# SCH.net
KiCad netlist of a schematic drawn in Altium Designer
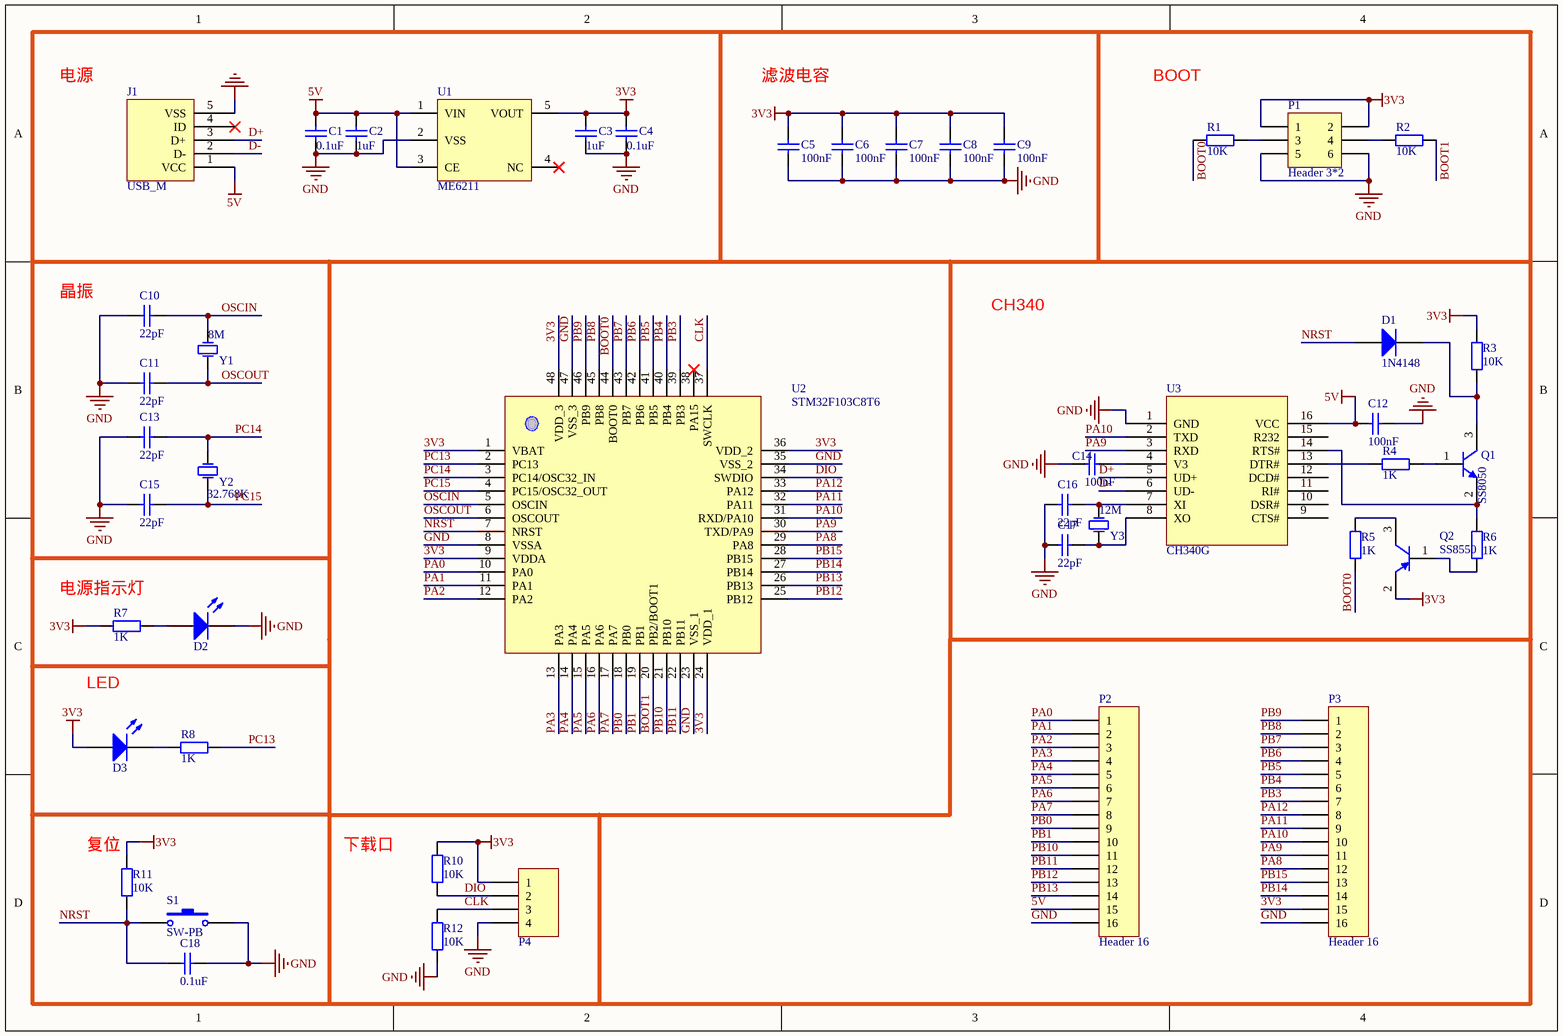
[diagram p0: SCH.SchDoc]

(export (version "E")
  (design (tool "Eeschema 10.0.6"))
  (components
    (comp (ref "C1")
      (value "0.1uF")
      (footprint "0603_C")
      (description "贴片电容")
      (fields (field (name "Comment") "Cap"))
      (libsource (lib "Miscellaneous Devices LC (1)") (part "0603 1uF (105) 10% 50V"))
    )
    (comp (ref "C2")
      (value "1uF")
      (footprint "0603_C")
      (description "贴片电容")
      (fields (field (name "Comment") "Cap"))
      (libsource (lib "Miscellaneous Devices LC (1)") (part "0603 1uF (105) 10% 50V"))
    )
    (comp (ref "C3")
      (value "1uF")
      (footprint "0603_C")
      (description "贴片电容")
      (fields (field (name "Comment") "Cap"))
      (libsource (lib "Miscellaneous Devices LC (1)") (part "0603 1uF (105) 10% 50V"))
    )
    (comp (ref "C4")
      (value "0.1uF")
      (footprint "0603_C")
      (description "贴片电容")
      (fields (field (name "Comment") "Cap"))
      (libsource (lib "Miscellaneous Devices LC (1)") (part "0603 1uF (105) 10% 50V"))
    )
    (comp (ref "C5")
      (value "100nF")
      (footprint "0603_C")
      (description "无极性电容")
      (fields (field (name "Comment") "Cap") (field (name "PUBLISHER") "Altium Limited"))
      (libsource (lib "fszhang") (part "Cap"))
    )
    (comp (ref "C6")
      (value "100nF")
      (footprint "0603_C")
      (description "无极性电容")
      (fields (field (name "Comment") "Cap") (field (name "PUBLISHER") "Altium Limited"))
      (libsource (lib "fszhang") (part "Cap"))
    )
    (comp (ref "C7")
      (value "100nF")
      (footprint "0603_C")
      (description "无极性电容")
      (fields (field (name "Comment") "Cap") (field (name "PUBLISHER") "Altium Limited"))
      (libsource (lib "fszhang") (part "Cap"))
    )
    (comp (ref "C8")
      (value "100nF")
      (footprint "0603_C")
      (description "无极性电容")
      (fields (field (name "Comment") "Cap") (field (name "PUBLISHER") "Altium Limited"))
      (libsource (lib "fszhang") (part "Cap"))
    )
    (comp (ref "C9")
      (value "100nF")
      (footprint "0603_C")
      (description "无极性电容")
      (fields (field (name "Comment") "Cap") (field (name "PUBLISHER") "Altium Limited"))
      (libsource (lib "fszhang") (part "Cap"))
    )
    (comp (ref "C10")
      (value "22pF")
      (footprint "0603_C")
      (description "无极性电容")
      (fields (field (name "Comment") "Cap") (field (name "PUBLISHER") "Altium Limited"))
      (libsource (lib "fszhang") (part "Cap"))
    )
    (comp (ref "C11")
      (value "22pF")
      (footprint "0603_C")
      (description "无极性电容")
      (fields (field (name "Comment") "Cap") (field (name "PUBLISHER") "Altium Limited"))
      (libsource (lib "fszhang") (part "Cap"))
    )
    (comp (ref "C12")
      (value "100nF")
      (footprint "0603_C")
      (description "无极性电容")
      (fields (field (name "Comment") "Cap") (field (name "PUBLISHER") "Altium Limited"))
      (libsource (lib "fszhang") (part "Cap"))
    )
    (comp (ref "C13")
      (value "22pF")
      (footprint "0603_C")
      (description "无极性电容")
      (fields (field (name "Comment") "Cap") (field (name "PUBLISHER") "Altium Limited"))
      (libsource (lib "fszhang") (part "Cap"))
    )
    (comp (ref "C14")
      (value "100nF")
      (footprint "0603_C")
      (description "无极性电容")
      (fields (field (name "Comment") "Cap") (field (name "PUBLISHER") "Altium Limited"))
      (libsource (lib "fszhang") (part "Cap"))
    )
    (comp (ref "C15")
      (value "22pF")
      (footprint "0603_C")
      (description "无极性电容")
      (fields (field (name "Comment") "Cap") (field (name "PUBLISHER") "Altium Limited"))
      (libsource (lib "fszhang") (part "Cap"))
    )
    (comp (ref "C16")
      (value "22pF")
      (footprint "0603_C")
      (description "无极性电容")
      (fields (field (name "Comment") "Cap") (field (name "PUBLISHER") "Altium Limited"))
      (libsource (lib "fszhang") (part "Cap"))
    )
    (comp (ref "C17")
      (value "22pF")
      (footprint "0603_C")
      (description "无极性电容")
      (fields (field (name "Comment") "Cap") (field (name "PUBLISHER") "Altium Limited"))
      (libsource (lib "fszhang") (part "Cap"))
    )
    (comp (ref "C18")
      (value "0.1uF")
      (footprint "0603_C")
      (description "贴片电容")
      (fields (field (name "Comment") "Cap"))
      (libsource (lib "Miscellaneous Devices LC (1)") (part "0603 1uF (105) 10% 50V"))
    )
    (comp (ref "D1")
      (value "Diode")
      (footprint "SOD-323")
      (description "二极管")
      (fields (field (name "TYPE") "1N4148") (field (name "PUBLISHER") "Altium Limited"))
      (libsource (lib "fszhang") (part "Diode"))
    )
    (comp (ref "D2")
      (value "LED0")
      (footprint "LED_0805_Blue")
      (description "发光二极管")
      (fields (field (name "PUBLISHER") "Altium Limited"))
      (libsource (lib "fszhang") (part "LED0"))
    )
    (comp (ref "D3")
      (value "LED0")
      (footprint "LED_0805_Blue")
      (description "发光二极管")
      (fields (field (name "PUBLISHER") "Altium Limited"))
      (libsource (lib "fszhang") (part "LED0"))
    )
    (comp (ref "J1")
      (value "USB_M")
      (footprint "USB")
      (description "MicroUSB接口")
      (libsource (lib "fszhang") (part "USB_M"))
    )
    (comp (ref "P1")
      (value "Header 3*2")
      (footprint "HDR3X2")
      (description "接插件")
      (libsource (lib "fszhang") (part "Header 3*2"))
    )
    (comp (ref "P2")
      (value "Header 16")
      (footprint "HDR16X1_A")
      (description "Header16贴片")
      (fields (field (name "PUBLISHER") "Altium Limited"))
      (libsource (lib "fszhang") (part "Header 16"))
    )
    (comp (ref "P3")
      (value "Header 16")
      (footprint "HDR16X1_A")
      (description "Header16贴片")
      (fields (field (name "PUBLISHER") "Altium Limited"))
      (libsource (lib "fszhang") (part "Header 16"))
    )
    (comp (ref "P4")
      (value "Header 4")
      (footprint "HDR4X1_A")
      (description "接插件")
      (fields (field (name "PUBLISHER") "Altium Limited"))
      (libsource (lib "fszhang") (part "Header 4"))
    )
    (comp (ref "Q1")
      (value "SS8050")
      (footprint "SOT-23")
      (description "NPN贴片三极管")
      (fields (field (name "PUBLISHER") "Altium Limited"))
      (libsource (lib "fszhang") (part "SS8050"))
    )
    (comp (ref "Q2")
      (value "SS8550")
      (footprint "SOT-23")
      (description "PNP贴片三极管")
      (fields (field (name "PUBLISHER") "Altium Limited"))
      (libsource (lib "fszhang") (part "SS8550"))
    )
    (comp (ref "R1")
      (value "10K")
      (footprint "0603_R")
      (description "贴片电阻")
      (fields (field (name "Comment") "Res1") (field (name "PUBLISHER") "Altium Limited"))
      (libsource (lib "") (part "Res1_3"))
    )
    (comp (ref "R2")
      (value "10K")
      (footprint "0603_R")
      (description "贴片电阻")
      (fields (field (name "Comment") "Res1") (field (name "PUBLISHER") "Altium Limited"))
      (libsource (lib "") (part "Res1_3"))
    )
    (comp (ref "R3")
      (value "10K")
      (footprint "0603_R")
      (description "贴片电阻")
      (fields (field (name "Comment") "Res1") (field (name "PUBLISHER") "Altium Limited"))
      (libsource (lib "fszhang") (part "Res1"))
    )
    (comp (ref "R4")
      (value "1K")
      (footprint "0603_R")
      (description "贴片电阻")
      (fields (field (name "Comment") "Res1") (field (name "PUBLISHER") "Altium Limited"))
      (libsource (lib "") (part "Res1_3"))
    )
    (comp (ref "R5")
      (value "1K")
      (footprint "0603_R")
      (description "贴片电阻")
      (fields (field (name "Comment") "Res1") (field (name "PUBLISHER") "Altium Limited"))
      (libsource (lib "fszhang") (part "Res1"))
    )
    (comp (ref "R6")
      (value "1K")
      (footprint "0603_R")
      (description "贴片电阻")
      (fields (field (name "Comment") "Res1") (field (name "PUBLISHER") "Altium Limited"))
      (libsource (lib "fszhang") (part "Res1"))
    )
    (comp (ref "R7")
      (value "1K")
      (footprint "0603_R")
      (description "贴片电阻")
      (fields (field (name "Comment") "Res1") (field (name "PUBLISHER") "Altium Limited"))
      (libsource (lib "") (part "Res1_2"))
    )
    (comp (ref "R8")
      (value "1K")
      (footprint "0603_R")
      (description "贴片电阻")
      (fields (field (name "Comment") "Res1") (field (name "PUBLISHER") "Altium Limited"))
      (libsource (lib "") (part "Res1_2"))
    )
    (comp (ref "R10")
      (value "10K")
      (footprint "0603_R")
      (description "贴片电阻")
      (fields (field (name "Comment") "Res1") (field (name "PUBLISHER") "Altium Limited"))
      (libsource (lib "") (part "Res1_1"))
    )
    (comp (ref "R11")
      (value "10K")
      (footprint "0603_R")
      (description "贴片电阻")
      (fields (field (name "Comment") "Res1") (field (name "PUBLISHER") "Altium Limited"))
      (libsource (lib "fszhang") (part "Res1"))
    )
    (comp (ref "R12")
      (value "10K")
      (footprint "0603_R")
      (description "贴片电阻")
      (fields (field (name "Comment") "Res1") (field (name "PUBLISHER") "Altium Limited"))
      (libsource (lib "") (part "Res1_1"))
    )
    (comp (ref "S1")
      (value "SW-PB")
      (footprint "SW_PB2_A1")
      (description "微动开关")
      (fields (field (name "PUBLISHER") "Altium Limited"))
      (libsource (lib "fszhang") (part "SW-PB"))
    )
    (comp (ref "U1") (value "ME6211") (footprint "SOT23-5") (libsource (lib "fszhang") (part "ME6211")))
    (comp (ref "U2")
      (value "STM32F103C8T6")
      (footprint "LQFP-48_M")
      (description "STM32单片机48引脚")
      (libsource (lib "fszhang") (part "STM32F103C8T6"))
    )
    (comp (ref "U3")
      (value "CH340G")
      (footprint "SOP-16")
      (description "串口芯片")
      (libsource (lib "fszhang") (part "CH340G"))
    )
    (comp (ref "Y1")
      (value "8M")
      (footprint "5032")
      (description "晶振")
      (fields (field (name "PUBLISHER") "Altium Limited"))
      (libsource (lib "fszhang") (part "XTAL"))
    )
    (comp (ref "Y2")
      (value "32.768K")
      (footprint "3215")
      (description "晶振")
      (fields (field (name "PUBLISHER") "Altium Limited"))
      (libsource (lib "fszhang") (part "XTAL"))
    )
    (comp (ref "Y3")
      (value "12M")
      (footprint "5032")
      (description "晶振")
      (fields (field (name "PUBLISHER") "Altium Limited"))
      (libsource (lib "fszhang") (part "XTAL"))
    )
  )
  (nets
    (net (code "1") (name "/BOOT0") (class "Default")
      (node (ref "R1") (pin "1") (pinfunction "1_1") (pintype "passive"))
      (node (ref "R5") (pin "1") (pinfunction "1_1") (pintype "passive"))
      (node (ref "U2") (pin "44") (pinfunction "BOOT0_44") (pintype "passive"))
    )
    (net (code "2") (name "/BOOT1") (class "Default")
      (node (ref "R2") (pin "2") (pinfunction "2_2") (pintype "passive"))
      (node (ref "U2") (pin "20") (pinfunction "PB2/BOOT1_20") (pintype "passive"))
    )
    (net (code "3") (name "/CLK") (class "Default")
      (node (ref "P4") (pin "3") (pinfunction "3_3") (pintype "passive"))
      (node (ref "R12") (pin "1") (pinfunction "1_1") (pintype "passive"))
      (node (ref "U2") (pin "37") (pinfunction "SWCLK_37") (pintype "passive"))
    )
    (net (code "4") (name "/D+") (class "Default")
      (node (ref "J1") (pin "3") (pinfunction "D+_3") (pintype "passive"))
      (node (ref "U3") (pin "5") (pinfunction "UD+_5") (pintype "passive"))
    )
    (net (code "5") (name "/D-") (class "Default")
      (node (ref "J1") (pin "2") (pinfunction "D-_2") (pintype "passive"))
      (node (ref "U3") (pin "6") (pinfunction "UD-_6") (pintype "passive"))
    )
    (net (code "6") (name "/DIO") (class "Default")
      (node (ref "P4") (pin "2") (pinfunction "2_2") (pintype "passive"))
      (node (ref "R10") (pin "2") (pinfunction "2_2") (pintype "passive"))
      (node (ref "U2") (pin "34") (pinfunction "SWDIO_34") (pintype "passive"))
    )
    (net (code "7") (name "/NRST") (class "Default")
      (node (ref "C18") (pin "2") (pinfunction "2_2") (pintype "passive"))
      (node (ref "D1") (pin "1") (pinfunction "A_1") (pintype "passive"))
      (node (ref "R11") (pin "1") (pinfunction "1_1") (pintype "passive"))
      (node (ref "S1") (pin "1") (pinfunction "1_1") (pintype "passive"))
      (node (ref "U2") (pin "7") (pinfunction "NRST_7") (pintype "passive"))
    )
    (net (code "8") (name "/OSCIN") (class "Default")
      (node (ref "C10") (pin "2") (pinfunction "2_2") (pintype "passive"))
      (node (ref "U2") (pin "5") (pinfunction "OSCIN_5") (pintype "passive"))
      (node (ref "Y1") (pin "1") (pinfunction "OSC1_1") (pintype "passive"))
    )
    (net (code "9") (name "/OSCOUT") (class "Default")
      (node (ref "C11") (pin "2") (pinfunction "2_2") (pintype "passive"))
      (node (ref "U2") (pin "6") (pinfunction "OSCOUT_6") (pintype "passive"))
      (node (ref "Y1") (pin "2") (pinfunction "OSC2_2") (pintype "passive"))
    )
    (net (code "10") (name "/PA0") (class "Default")
      (node (ref "P2") (pin "1") (pinfunction "1_1") (pintype "passive"))
      (node (ref "U2") (pin "10") (pinfunction "PA0_10") (pintype "passive"))
    )
    (net (code "11") (name "/PA1") (class "Default")
      (node (ref "P2") (pin "2") (pinfunction "2_2") (pintype "passive"))
      (node (ref "U2") (pin "11") (pinfunction "PA1_11") (pintype "passive"))
    )
    (net (code "12") (name "/PA2") (class "Default")
      (node (ref "P2") (pin "3") (pinfunction "3_3") (pintype "passive"))
      (node (ref "U2") (pin "12") (pinfunction "PA2_12") (pintype "passive"))
    )
    (net (code "13") (name "/PA3") (class "Default")
      (node (ref "P2") (pin "4") (pinfunction "4_4") (pintype "passive"))
      (node (ref "U2") (pin "13") (pinfunction "PA3_13") (pintype "passive"))
    )
    (net (code "14") (name "/PA4") (class "Default")
      (node (ref "P2") (pin "5") (pinfunction "5_5") (pintype "passive"))
      (node (ref "U2") (pin "14") (pinfunction "PA4_14") (pintype "passive"))
    )
    (net (code "15") (name "/PA5") (class "Default")
      (node (ref "P2") (pin "6") (pinfunction "6_6") (pintype "passive"))
      (node (ref "U2") (pin "15") (pinfunction "PA5_15") (pintype "passive"))
    )
    (net (code "16") (name "/PA6") (class "Default")
      (node (ref "P2") (pin "7") (pinfunction "7_7") (pintype "passive"))
      (node (ref "U2") (pin "16") (pinfunction "PA6_16") (pintype "passive"))
    )
    (net (code "17") (name "/PA7") (class "Default")
      (node (ref "P2") (pin "8") (pinfunction "8_8") (pintype "passive"))
      (node (ref "U2") (pin "17") (pinfunction "PA7_17") (pintype "passive"))
    )
    (net (code "18") (name "/PA8") (class "Default")
      (node (ref "P3") (pin "12") (pinfunction "12_12") (pintype "passive"))
      (node (ref "U2") (pin "29") (pinfunction "PA8_29") (pintype "passive"))
    )
    (net (code "19") (name "/PA9") (class "Default")
      (node (ref "P3") (pin "11") (pinfunction "11_11") (pintype "passive"))
      (node (ref "U2") (pin "30") (pinfunction "TXD/PA9_30") (pintype "passive"))
      (node (ref "U3") (pin "3") (pinfunction "RXD_3") (pintype "passive"))
    )
    (net (code "20") (name "/PA10") (class "Default")
      (node (ref "P3") (pin "10") (pinfunction "10_10") (pintype "passive"))
      (node (ref "U2") (pin "31") (pinfunction "RXD/PA10_31") (pintype "passive"))
      (node (ref "U3") (pin "2") (pinfunction "TXD_2") (pintype "passive"))
    )
    (net (code "21") (name "/PA11") (class "Default")
      (node (ref "P3") (pin "9") (pinfunction "9_9") (pintype "passive"))
      (node (ref "U2") (pin "32") (pinfunction "PA11_32") (pintype "passive"))
    )
    (net (code "22") (name "/PA12") (class "Default")
      (node (ref "P3") (pin "8") (pinfunction "8_8") (pintype "passive"))
      (node (ref "U2") (pin "33") (pinfunction "PA12_33") (pintype "passive"))
    )
    (net (code "23") (name "/PB0") (class "Default")
      (node (ref "P2") (pin "9") (pinfunction "9_9") (pintype "passive"))
      (node (ref "U2") (pin "18") (pinfunction "PB0_18") (pintype "passive"))
    )
    (net (code "24") (name "/PB1") (class "Default")
      (node (ref "P2") (pin "10") (pinfunction "10_10") (pintype "passive"))
      (node (ref "U2") (pin "19") (pinfunction "PB1_19") (pintype "passive"))
    )
    (net (code "25") (name "/PB3") (class "Default")
      (node (ref "P3") (pin "7") (pinfunction "7_7") (pintype "passive"))
      (node (ref "U2") (pin "39") (pinfunction "PB3_39") (pintype "passive"))
    )
    (net (code "26") (name "/PB4") (class "Default")
      (node (ref "P3") (pin "6") (pinfunction "6_6") (pintype "passive"))
      (node (ref "U2") (pin "40") (pinfunction "PB4_40") (pintype "passive"))
    )
    (net (code "27") (name "/PB5") (class "Default")
      (node (ref "P3") (pin "5") (pinfunction "5_5") (pintype "passive"))
      (node (ref "U2") (pin "41") (pinfunction "PB5_41") (pintype "passive"))
    )
    (net (code "28") (name "/PB6") (class "Default")
      (node (ref "P3") (pin "4") (pinfunction "4_4") (pintype "passive"))
      (node (ref "U2") (pin "42") (pinfunction "PB6_42") (pintype "passive"))
    )
    (net (code "29") (name "/PB7") (class "Default")
      (node (ref "P3") (pin "3") (pinfunction "3_3") (pintype "passive"))
      (node (ref "U2") (pin "43") (pinfunction "PB7_43") (pintype "passive"))
    )
    (net (code "30") (name "/PB8") (class "Default")
      (node (ref "P3") (pin "2") (pinfunction "2_2") (pintype "passive"))
      (node (ref "U2") (pin "45") (pinfunction "PB8_45") (pintype "passive"))
    )
    (net (code "31") (name "/PB9") (class "Default")
      (node (ref "P3") (pin "1") (pinfunction "1_1") (pintype "passive"))
      (node (ref "U2") (pin "46") (pinfunction "PB9_46") (pintype "passive"))
    )
    (net (code "32") (name "/PB10") (class "Default")
      (node (ref "P2") (pin "11") (pinfunction "11_11") (pintype "passive"))
      (node (ref "U2") (pin "21") (pinfunction "PB10_21") (pintype "passive"))
    )
    (net (code "33") (name "/PB11") (class "Default")
      (node (ref "P2") (pin "12") (pinfunction "12_12") (pintype "passive"))
      (node (ref "U2") (pin "22") (pinfunction "PB11_22") (pintype "passive"))
    )
    (net (code "34") (name "/PB12") (class "Default")
      (node (ref "P2") (pin "13") (pinfunction "13_13") (pintype "passive"))
      (node (ref "U2") (pin "25") (pinfunction "PB12_25") (pintype "passive"))
    )
    (net (code "35") (name "/PB13") (class "Default")
      (node (ref "P2") (pin "14") (pinfunction "14_14") (pintype "passive"))
      (node (ref "U2") (pin "26") (pinfunction "PB13_26") (pintype "passive"))
    )
    (net (code "36") (name "/PB14") (class "Default")
      (node (ref "P3") (pin "14") (pinfunction "14_14") (pintype "passive"))
      (node (ref "U2") (pin "27") (pinfunction "PB14_27") (pintype "passive"))
    )
    (net (code "37") (name "/PB15") (class "Default")
      (node (ref "P3") (pin "13") (pinfunction "13_13") (pintype "passive"))
      (node (ref "U2") (pin "28") (pinfunction "PB15_28") (pintype "passive"))
    )
    (net (code "38") (name "/PC13") (class "Default")
      (node (ref "R8") (pin "1") (pinfunction "1_1") (pintype "passive"))
      (node (ref "U2") (pin "2") (pinfunction "PC13_2") (pintype "passive"))
    )
    (net (code "39") (name "/PC14") (class "Default")
      (node (ref "C13") (pin "2") (pinfunction "2_2") (pintype "passive"))
      (node (ref "U2") (pin "3") (pinfunction "PC14/OSC32_IN_3") (pintype "passive"))
      (node (ref "Y2") (pin "1") (pinfunction "OSC1_1") (pintype "passive"))
    )
    (net (code "40") (name "/PC15") (class "Default")
      (node (ref "C15") (pin "2") (pinfunction "2_2") (pintype "passive"))
      (node (ref "U2") (pin "4") (pinfunction "PC15/OSC32_OUT_4") (pintype "passive"))
      (node (ref "Y2") (pin "2") (pinfunction "OSC2_2") (pintype "passive"))
    )
    (net (code "41") (name "3V3") (class "Default")
      (node (ref "C3") (pin "2") (pinfunction "2_2") (pintype "passive"))
      (node (ref "C4") (pin "2") (pinfunction "2_2") (pintype "passive"))
      (node (ref "C5") (pin "2") (pinfunction "2_2") (pintype "passive"))
      (node (ref "C6") (pin "2") (pinfunction "2_2") (pintype "passive"))
      (node (ref "C7") (pin "2") (pinfunction "2_2") (pintype "passive"))
      (node (ref "C8") (pin "2") (pinfunction "2_2") (pintype "passive"))
      (node (ref "C9") (pin "2") (pinfunction "2_2") (pintype "passive"))
      (node (ref "D3") (pin "1") (pinfunction "A_1") (pintype "passive"))
      (node (ref "P1") (pin "1") (pinfunction "1_1") (pintype "passive"))
      (node (ref "P1") (pin "2") (pinfunction "2_2") (pintype "passive"))
      (node (ref "P3") (pin "15") (pinfunction "15_15") (pintype "passive"))
      (node (ref "P4") (pin "1") (pinfunction "1_1") (pintype "passive"))
      (node (ref "Q2") (pin "2") (pinfunction "E_2") (pintype "passive"))
      (node (ref "R10") (pin "1") (pinfunction "1_1") (pintype "passive"))
      (node (ref "R11") (pin "2") (pinfunction "2_2") (pintype "passive"))
      (node (ref "R3") (pin "2") (pinfunction "2_2") (pintype "passive"))
      (node (ref "R7") (pin "2") (pinfunction "2_2") (pintype "passive"))
      (node (ref "U1") (pin "5") (pinfunction "VOUT_5") (pintype "passive"))
      (node (ref "U2") (pin "1") (pinfunction "VBAT_1") (pintype "passive"))
      (node (ref "U2") (pin "24") (pinfunction "VDD_1_24") (pintype "passive"))
      (node (ref "U2") (pin "36") (pinfunction "VDD_2_36") (pintype "passive"))
      (node (ref "U2") (pin "48") (pinfunction "VDD_3_48") (pintype "passive"))
      (node (ref "U2") (pin "9") (pinfunction "VDDA_9") (pintype "passive"))
    )
    (net (code "42") (name "5V") (class "Default")
      (node (ref "C1") (pin "2") (pinfunction "2_2") (pintype "passive"))
      (node (ref "C12") (pin "2") (pinfunction "2_2") (pintype "passive"))
      (node (ref "C2") (pin "2") (pinfunction "2_2") (pintype "passive"))
      (node (ref "J1") (pin "1") (pinfunction "VCC_1") (pintype "passive"))
      (node (ref "P2") (pin "15") (pinfunction "15_15") (pintype "passive"))
      (node (ref "U1") (pin "1") (pinfunction "VIN_1") (pintype "passive"))
      (node (ref "U1") (pin "3") (pinfunction "CE_3") (pintype "passive"))
      (node (ref "U3") (pin "16") (pinfunction "VCC_16") (pintype "power_in"))
    )
    (net (code "43") (name "GND") (class "Default")
      (node (ref "C1") (pin "1") (pinfunction "1_1") (pintype "passive"))
      (node (ref "C10") (pin "1") (pinfunction "1_1") (pintype "passive"))
      (node (ref "C11") (pin "1") (pinfunction "1_1") (pintype "passive"))
      (node (ref "C12") (pin "1") (pinfunction "1_1") (pintype "passive"))
      (node (ref "C13") (pin "1") (pinfunction "1_1") (pintype "passive"))
      (node (ref "C14") (pin "2") (pinfunction "2_2") (pintype "passive"))
      (node (ref "C15") (pin "1") (pinfunction "1_1") (pintype "passive"))
      (node (ref "C16") (pin "1") (pinfunction "1_1") (pintype "passive"))
      (node (ref "C17") (pin "1") (pinfunction "1_1") (pintype "passive"))
      (node (ref "C18") (pin "1") (pinfunction "1_1") (pintype "passive"))
      (node (ref "C2") (pin "1") (pinfunction "1_1") (pintype "passive"))
      (node (ref "C3") (pin "1") (pinfunction "1_1") (pintype "passive"))
      (node (ref "C4") (pin "1") (pinfunction "1_1") (pintype "passive"))
      (node (ref "C5") (pin "1") (pinfunction "1_1") (pintype "passive"))
      (node (ref "C6") (pin "1") (pinfunction "1_1") (pintype "passive"))
      (node (ref "C7") (pin "1") (pinfunction "1_1") (pintype "passive"))
      (node (ref "C8") (pin "1") (pinfunction "1_1") (pintype "passive"))
      (node (ref "C9") (pin "1") (pinfunction "1_1") (pintype "passive"))
      (node (ref "D2") (pin "2") (pinfunction "K_2") (pintype "passive"))
      (node (ref "J1") (pin "5") (pinfunction "VSS_5") (pintype "passive"))
      (node (ref "P1") (pin "5") (pinfunction "5_5") (pintype "passive"))
      (node (ref "P1") (pin "6") (pinfunction "6_6") (pintype "passive"))
      (node (ref "P2") (pin "16") (pinfunction "16_16") (pintype "passive"))
      (node (ref "P3") (pin "16") (pinfunction "16_16") (pintype "passive"))
      (node (ref "P4") (pin "4") (pinfunction "4_4") (pintype "passive"))
      (node (ref "R12") (pin "2") (pinfunction "2_2") (pintype "passive"))
      (node (ref "S1") (pin "2") (pinfunction "2_2") (pintype "passive"))
      (node (ref "U1") (pin "2") (pinfunction "VSS_2") (pintype "passive"))
      (node (ref "U2") (pin "23") (pinfunction "VSS_1_23") (pintype "passive"))
      (node (ref "U2") (pin "35") (pinfunction "VSS_2_35") (pintype "passive"))
      (node (ref "U2") (pin "47") (pinfunction "VSS_3_47") (pintype "passive"))
      (node (ref "U2") (pin "8") (pinfunction "VSSA_8") (pintype "passive"))
      (node (ref "U3") (pin "1") (pinfunction "GND_1") (pintype "power_in"))
    )
    (net (code "44") (name "Net-(D1-K)") (class "Default")
      (node (ref "D1") (pin "2") (pinfunction "K_2") (pintype "passive"))
      (node (ref "Q1") (pin "3") (pinfunction "C_3") (pintype "passive"))
      (node (ref "R3") (pin "1") (pinfunction "1_1") (pintype "passive"))
    )
    (net (code "45") (name "Net-(D2-A)") (class "Default")
      (node (ref "D2") (pin "1") (pinfunction "A_1") (pintype "passive"))
      (node (ref "R7") (pin "1") (pinfunction "1_1") (pintype "passive"))
    )
    (net (code "46") (name "Net-(D3-K)") (class "Default")
      (node (ref "D3") (pin "2") (pinfunction "K_2") (pintype "passive"))
      (node (ref "R8") (pin "2") (pinfunction "2_2") (pintype "passive"))
    )
    (net (code "47") (name "Net-(P1-Pad3)") (class "Default")
      (node (ref "P1") (pin "3") (pinfunction "3_3") (pintype "passive"))
      (node (ref "R1") (pin "2") (pinfunction "2_2") (pintype "passive"))
    )
    (net (code "48") (name "Net-(P1-Pad4)") (class "Default")
      (node (ref "P1") (pin "4") (pinfunction "4_4") (pintype "passive"))
      (node (ref "R2") (pin "1") (pinfunction "1_1") (pintype "passive"))
    )
    (net (code "49") (name "Net-(Q1-B)") (class "Default")
      (node (ref "Q1") (pin "1") (pinfunction "B_1") (pintype "passive"))
      (node (ref "R4") (pin "2") (pinfunction "2_2") (pintype "passive"))
    )
    (net (code "50") (name "Net-(Q1-E)") (class "Default")
      (node (ref "Q1") (pin "2") (pinfunction "E_2") (pintype "passive"))
      (node (ref "R6") (pin "2") (pinfunction "2_2") (pintype "passive"))
      (node (ref "U3") (pin "14") (pinfunction "RTS#_14") (pintype "passive"))
    )
    (net (code "51") (name "Net-(Q2-B)") (class "Default")
      (node (ref "Q2") (pin "1") (pinfunction "B_1") (pintype "passive"))
      (node (ref "R6") (pin "1") (pinfunction "1_1") (pintype "passive"))
    )
    (net (code "52") (name "Net-(Q2-C)") (class "Default")
      (node (ref "Q2") (pin "3") (pinfunction "C_3") (pintype "passive"))
      (node (ref "R5") (pin "2") (pinfunction "2_2") (pintype "passive"))
    )
    (net (code "53") (name "Net-(U3-DTR#)") (class "Default")
      (node (ref "R4") (pin "1") (pinfunction "1_1") (pintype "passive"))
      (node (ref "U3") (pin "13") (pinfunction "DTR#_13") (pintype "passive"))
    )
    (net (code "54") (name "Net-(U3-V3)") (class "Default")
      (node (ref "C14") (pin "1") (pinfunction "1_1") (pintype "passive"))
      (node (ref "U3") (pin "4") (pinfunction "V3_4") (pintype "power_in"))
    )
    (net (code "55") (name "Net-(U3-XI)") (class "Default")
      (node (ref "C16") (pin "2") (pinfunction "2_2") (pintype "passive"))
      (node (ref "U3") (pin "7") (pinfunction "XI_7") (pintype "passive"))
      (node (ref "Y3") (pin "1") (pinfunction "OSC1_1") (pintype "passive"))
    )
    (net (code "56") (name "Net-(U3-XO)") (class "Default")
      (node (ref "C17") (pin "2") (pinfunction "2_2") (pintype "passive"))
      (node (ref "U3") (pin "8") (pinfunction "XO_8") (pintype "passive"))
      (node (ref "Y3") (pin "2") (pinfunction "OSC2_2") (pintype "passive"))
    )
    (net (code "57") (name "unconnected-(J1-ID-Pad4)") (class "Default")
      (node (ref "J1") (pin "4") (pinfunction "ID_4") (pintype "passive+no_connect"))
    )
    (net (code "58") (name "unconnected-(U1-NC-Pad4)") (class "Default")
      (node (ref "U1") (pin "4") (pinfunction "NC_4") (pintype "passive+no_connect"))
    )
    (net (code "59") (name "unconnected-(U2-PA15-Pad38)") (class "Default")
      (node (ref "U2") (pin "38") (pinfunction "PA15_38") (pintype "passive+no_connect"))
    )
    (net (code "60") (name "unconnected-(U3-CTS#-Pad9)") (class "Default")
      (node (ref "U3") (pin "9") (pinfunction "CTS#_9") (pintype "passive"))
    )
    (net (code "61") (name "unconnected-(U3-DCD#-Pad12)") (class "Default")
      (node (ref "U3") (pin "12") (pinfunction "DCD#_12") (pintype "passive"))
    )
    (net (code "62") (name "unconnected-(U3-DSR#-Pad10)") (class "Default")
      (node (ref "U3") (pin "10") (pinfunction "DSR#_10") (pintype "passive"))
    )
    (net (code "63") (name "unconnected-(U3-R232-Pad15)") (class "Default")
      (node (ref "U3") (pin "15") (pinfunction "R232_15") (pintype "passive"))
    )
    (net (code "64") (name "unconnected-(U3-RI#-Pad11)") (class "Default")
      (node (ref "U3") (pin "11") (pinfunction "RI#_11") (pintype "passive"))
    )
  )
)
